# AudioPreAmp-LM741.net
KiCad netlist of a schematic drawn in EAGLE
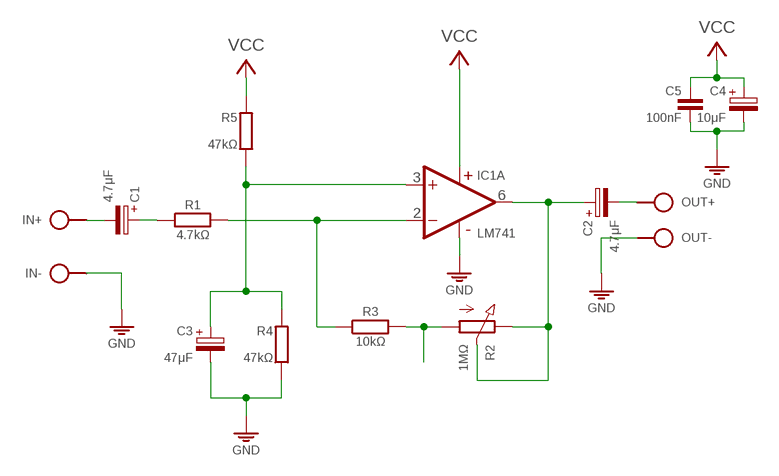
[diagram p0: schematic, sheet 1]

(export (version "E")
  (design (tool "Eeschema 10.0.6"))
  (components
    (comp (ref "C1")
      (value "4.7μF")
      (footprint "eagle-import:E2.5-4_V")
      (libsource (lib "eagle-import") (part "CPOLE2,5-4/V"))
    )
    (comp (ref "C2")
      (value "4.7μF")
      (footprint "eagle-import:E2,5-4")
      (libsource (lib "eagle-import") (part "CPOLE2,5-4"))
    )
    (comp (ref "C3")
      (value "47μF")
      (footprint "eagle-import:E2,5-4")
      (libsource (lib "eagle-import") (part "CPOLE2,5-4"))
    )
    (comp (ref "C4")
      (value "10μF")
      (footprint "eagle-import:E2,5-4")
      (libsource (lib "eagle-import") (part "CPOLE2,5-4"))
    )
    (comp (ref "C5")
      (value "100nF")
      (footprint "eagle-import:C050-020X044_V")
      (libsource (lib "eagle-import") (part "C050-020X044/V"))
    )
    (comp (ref "IC1")
      (value "LM741")
      (footprint "eagle-import:DIL08")
      (libsource (lib "eagle-import") (part "LM741"))
    )
    (comp (ref "IN")
      (value "SPAD+--+")
      (footprint "eagle-import:SPAD-+")
      (libsource (lib "eagle-import") (part "SPAD+--+"))
    )
    (comp (ref "OUT")
      (value "SPAD+-+-")
      (footprint "eagle-import:SPAD+-")
      (libsource (lib "eagle-import") (part "SPAD+-+-"))
    )
    (comp (ref "PWR")
      (value "VCC_GNDL")
      (footprint "eagle-import:SPAD-+")
      (libsource (lib "eagle-import") (part "VCC_GNDL"))
    )
    (comp (ref "R1")
      (value "4.7kΩ")
      (footprint "eagle-import:0204_10")
      (libsource (lib "eagle-import") (part "R-H0204/10"))
    )
    (comp (ref "R2")
      (value "1MΩ")
      (footprint "eagle-import:POT-P5")
      (libsource (lib "eagle-import") (part "POT-P5"))
    )
    (comp (ref "R3")
      (value "10kΩ")
      (footprint "eagle-import:0204_10-V")
      (libsource (lib "eagle-import") (part "R-H0204/10-V"))
    )
    (comp (ref "R4")
      (value "47kΩ")
      (footprint "eagle-import:0204_10-V")
      (libsource (lib "eagle-import") (part "R0204/10-V"))
    )
    (comp (ref "R5")
      (value "47kΩ")
      (footprint "eagle-import:0204_10")
      (libsource (lib "eagle-import") (part "R0204/10"))
    )
  )
  (nets
    (net (code "1") (name "GND") (class "Default")
      (node (ref "C3") (pin "-") (pinfunction "-_-") (pintype "passive"))
      (node (ref "C4") (pin "-") (pinfunction "-_-") (pintype "passive"))
      (node (ref "C5") (pin "2") (pinfunction "2_2") (pintype "passive"))
      (node (ref "IC1") (pin "4") (pinfunction "V-_4") (pintype "power_in"))
      (node (ref "IN") (pin "1") (pinfunction "P$1_1") (pintype "passive"))
      (node (ref "OUT") (pin "1") (pinfunction "P$1_1") (pintype "passive"))
      (node (ref "PWR") (pin "1") (pinfunction "GND_1") (pintype "power_in"))
      (node (ref "R4") (pin "2") (pinfunction "2_2") (pintype "passive"))
    )
    (net (code "2") (name "Net-(C1-Pad+)") (class "Default")
      (node (ref "C1") (pin "+") (pinfunction "+_+") (pintype "passive"))
      (node (ref "R1") (pin "1") (pinfunction "1_1") (pintype "passive"))
    )
    (net (code "3") (name "Net-(IC1B-+IN)") (class "Default")
      (node (ref "C3") (pin "+") (pinfunction "+_+") (pintype "passive"))
      (node (ref "IC1") (pin "3") (pinfunction "+IN_3") (pintype "input"))
      (node (ref "R4") (pin "1") (pinfunction "1_1") (pintype "passive"))
      (node (ref "R5") (pin "1") (pinfunction "2_1") (pintype "passive"))
    )
    (net (code "4") (name "Net-(IC1B--IN)") (class "Default")
      (node (ref "IC1") (pin "2") (pinfunction "-IN_2") (pintype "input"))
      (node (ref "R1") (pin "2") (pinfunction "2_2") (pintype "passive"))
      (node (ref "R3") (pin "1") (pinfunction "1_1") (pintype "passive"))
    )
    (net (code "5") (name "Net-(IC1B-OUT)") (class "Default")
      (node (ref "C2") (pin "+") (pinfunction "+_+") (pintype "passive"))
      (node (ref "IC1") (pin "6") (pinfunction "OUT_6") (pintype "output"))
      (node (ref "R2") (pin "E") (pinfunction "E_E") (pintype "passive"))
      (node (ref "R2") (pin "S") (pinfunction "S_S") (pintype "passive"))
    )
    (net (code "6") (name "Net-(INA-P$1)") (class "Default")
      (node (ref "C1") (pin "-") (pinfunction "-_-") (pintype "passive"))
      (node (ref "IN") (pin "2") (pinfunction "P$1_2") (pintype "passive"))
    )
    (net (code "7") (name "Net-(OUTA-P$1)") (class "Default")
      (node (ref "C2") (pin "-") (pinfunction "-_-") (pintype "passive"))
      (node (ref "OUT") (pin "2") (pinfunction "P$1_2") (pintype "passive"))
    )
    (net (code "8") (name "Net-(R2-PadA)") (class "Default")
      (node (ref "R2") (pin "A") (pinfunction "A_A") (pintype "passive"))
      (node (ref "R3") (pin "2") (pinfunction "2_2") (pintype "passive"))
    )
    (net (code "9") (name "VCC") (class "Default")
      (node (ref "C4") (pin "+") (pinfunction "+_+") (pintype "passive"))
      (node (ref "C5") (pin "1") (pinfunction "1_1") (pintype "passive"))
      (node (ref "IC1") (pin "7") (pinfunction "V+_7") (pintype "power_in"))
      (node (ref "PWR") (pin "2") (pinfunction "VCC_2") (pintype "power_in"))
      (node (ref "R5") (pin "2") (pinfunction "1_2") (pintype "passive"))
    )
  )
)
